# BMS_Carrier_-_Firmware_Contactor_Control.net
KiCad netlist of a schematic drawn in Altium Designer
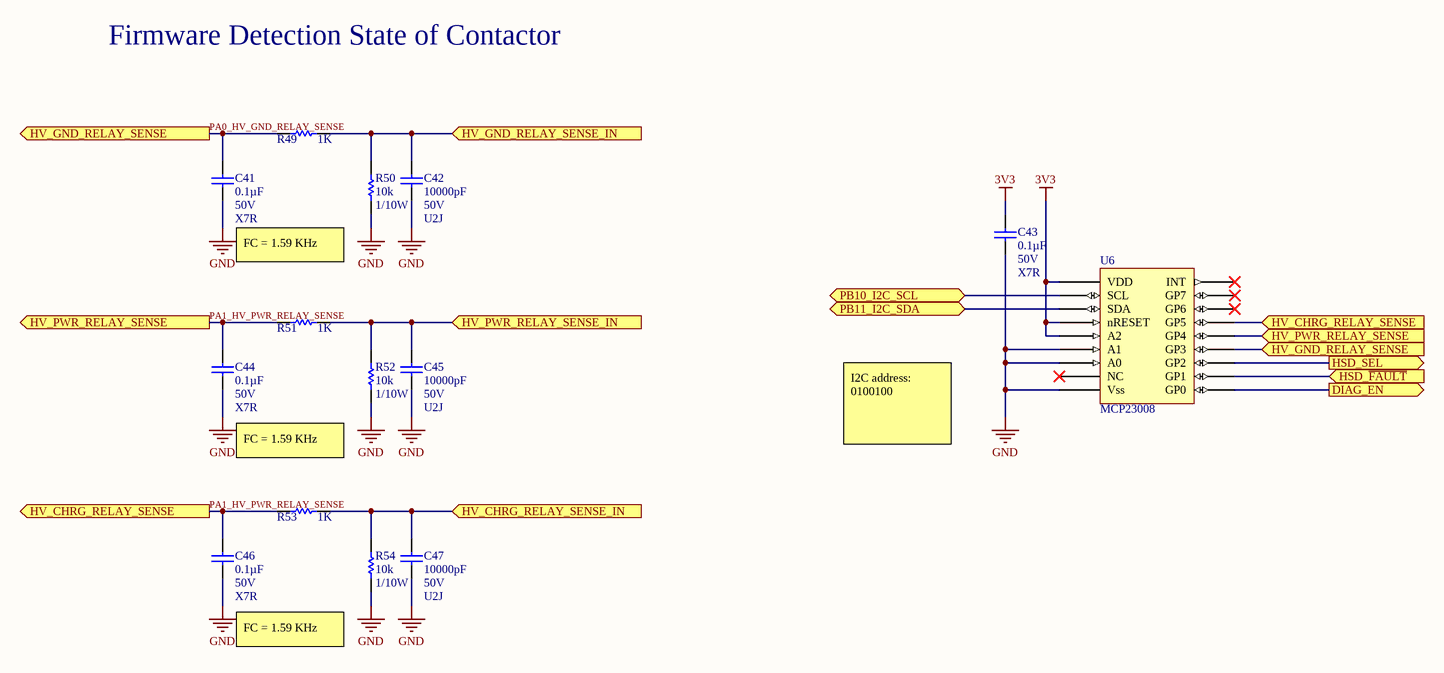
[diagram p0: BMS Carrier - Firmware Contactor Control.SchDoc]

(export (version "E")
  (design (tool "Eeschema 10.0.6"))
  (components
    (comp (ref "C41")
      (value "CAP CER 0.1UF 50V 10% X7R 0603")
      (footprint "CAP, 0603")
      (description "0.10µF ±10% 50V Ceramic Capacitor X7R 0603 (1608 Metric)")
      (fields
        (field (name "TOLERANCE") "±10%")
        (field (name "CAPACITANCE") "0.1µF")
        (field (name "VOLTAGE") "50V")
        (field (name "TEMPERATURE COEFFICIENT") "X7R")
      )
      (libsource (lib "Schematic Diagrams") (part "CAP CER 0.1UF 50V 10% X7R 0603"))
    )
    (comp (ref "C42")
      (value "CAP CER 10nF 50V 5% X7R 0603")
      (footprint "CAP, 0603")
      (description "10000pF ±5% 50V Ceramic Capacitor U2J 0603 (1608 Metric)")
      (fields
        (field (name "TOLERANCE") "±5%")
        (field (name "CAPACITANCE") "10000pF")
        (field (name "VOLTAGE") "50V")
        (field (name "TEMPERATURE COEFFICIENT") "U2J")
      )
      (libsource (lib "Schematic Diagrams") (part "CAP CER 10nF 50V 5% X7R 0603"))
    )
    (comp (ref "C43")
      (value "CAP CER 0.1UF 50V 10% X7R 0603")
      (footprint "CAP, 0603")
      (description "0.10µF ±10% 50V Ceramic Capacitor X7R 0603 (1608 Metric)")
      (fields
        (field (name "TOLERANCE") "±10%")
        (field (name "CAPACITANCE") "0.1µF")
        (field (name "VOLTAGE") "50V")
        (field (name "TEMPERATURE COEFFICIENT") "X7R")
      )
      (libsource (lib "Schematic Diagrams") (part "CAP CER 0.1UF 50V 10% X7R 0603"))
    )
    (comp (ref "C44")
      (value "CAP CER 0.1UF 50V 10% X7R 0603")
      (footprint "CAP, 0603")
      (description "0.10µF ±10% 50V Ceramic Capacitor X7R 0603 (1608 Metric)")
      (fields
        (field (name "TOLERANCE") "±10%")
        (field (name "CAPACITANCE") "0.1µF")
        (field (name "VOLTAGE") "50V")
        (field (name "TEMPERATURE COEFFICIENT") "X7R")
      )
      (libsource (lib "Schematic Diagrams") (part "CAP CER 0.1UF 50V 10% X7R 0603"))
    )
    (comp (ref "C45")
      (value "CAP CER 10nF 50V 5% X7R 0603")
      (footprint "CAP, 0603")
      (description "10000pF ±5% 50V Ceramic Capacitor U2J 0603 (1608 Metric)")
      (fields
        (field (name "TOLERANCE") "±5%")
        (field (name "CAPACITANCE") "10000pF")
        (field (name "VOLTAGE") "50V")
        (field (name "TEMPERATURE COEFFICIENT") "U2J")
      )
      (libsource (lib "Schematic Diagrams") (part "CAP CER 10nF 50V 5% X7R 0603"))
    )
    (comp (ref "C46")
      (value "CAP CER 0.1UF 50V 10% X7R 0603")
      (footprint "CAP, 0603")
      (description "0.10µF ±10% 50V Ceramic Capacitor X7R 0603 (1608 Metric)")
      (fields
        (field (name "TOLERANCE") "±10%")
        (field (name "CAPACITANCE") "0.1µF")
        (field (name "VOLTAGE") "50V")
        (field (name "TEMPERATURE COEFFICIENT") "X7R")
      )
      (libsource (lib "Schematic Diagrams") (part "CAP CER 0.1UF 50V 10% X7R 0603"))
    )
    (comp (ref "C47")
      (value "CAP CER 10nF 50V 5% X7R 0603")
      (footprint "CAP, 0603")
      (description "10000pF ±5% 50V Ceramic Capacitor U2J 0603 (1608 Metric)")
      (fields
        (field (name "TOLERANCE") "±5%")
        (field (name "CAPACITANCE") "10000pF")
        (field (name "VOLTAGE") "50V")
        (field (name "TEMPERATURE COEFFICIENT") "U2J")
      )
      (libsource (lib "Schematic Diagrams") (part "CAP CER 10nF 50V 5% X7R 0603"))
    )
    (comp (ref "R49")
      (value "1K")
      (footprint "RES, 0603")
      (description "1k Ohm ±5% 0.1W, 1/10W Chip Resistor 0603 (1608 Metric)")
      (fields
        (field (name "MANUFACTURER") "Yageo")
        (field (name "MANUFACTURER PART NUMBER") "RC0603JR-071KL")
      )
      (libsource (lib "Schematic Diagrams") (part "RES 1K OHM 5% 1/10W 0603"))
    )
    (comp (ref "R50")
      (value "RES 10K OHM 1% 1/10W 0603")
      (footprint "RES, 0603")
      (description "RES SMD 10K OHM 1% 1/10W 0603")
      (fields
        (field (name "TOLERANCE") "±1%")
        (field (name "RESISTANCE") "10k")
        (field (name "POWER") "1/10W")
      )
      (libsource (lib "Schematic Diagrams") (part "RES 10K OHM 1% 1/10W 0603"))
    )
    (comp (ref "R51")
      (value "1K")
      (footprint "RES, 0603")
      (description "1k Ohm ±5% 0.1W, 1/10W Chip Resistor 0603 (1608 Metric)")
      (fields
        (field (name "MANUFACTURER") "Yageo")
        (field (name "MANUFACTURER PART NUMBER") "RC0603JR-071KL")
      )
      (libsource (lib "Schematic Diagrams") (part "RES 1K OHM 5% 1/10W 0603"))
    )
    (comp (ref "R52")
      (value "RES 10K OHM 1% 1/10W 0603")
      (footprint "RES, 0603")
      (description "RES SMD 10K OHM 1% 1/10W 0603")
      (fields
        (field (name "TOLERANCE") "±1%")
        (field (name "RESISTANCE") "10k")
        (field (name "POWER") "1/10W")
      )
      (libsource (lib "Schematic Diagrams") (part "RES 10K OHM 1% 1/10W 0603"))
    )
    (comp (ref "R53")
      (value "1K")
      (footprint "RES, 0603")
      (description "1k Ohm ±5% 0.1W, 1/10W Chip Resistor 0603 (1608 Metric)")
      (fields
        (field (name "MANUFACTURER") "Yageo")
        (field (name "MANUFACTURER PART NUMBER") "RC0603JR-071KL")
      )
      (libsource (lib "Schematic Diagrams") (part "RES 1K OHM 5% 1/10W 0603"))
    )
    (comp (ref "R54")
      (value "RES 10K OHM 1% 1/10W 0603")
      (footprint "RES, 0603")
      (description "RES SMD 10K OHM 1% 1/10W 0603")
      (fields
        (field (name "TOLERANCE") "±1%")
        (field (name "RESISTANCE") "10k")
        (field (name "POWER") "1/10W")
      )
      (libsource (lib "Schematic Diagrams") (part "RES 10K OHM 1% 1/10W 0603"))
    )
    (comp (ref "U6")
      (value "MCP23008")
      (footprint "IC 18SOIC")
      (description "MCP23008 I/O Expander 8B+1Int 18P SOIC")
      (fields
        (field (name "MANUFACTURER") "Microchip Technology")
        (field (name "MANUFACTURER PART NUMBER") "MCP23008T-E/SO")
      )
      (libsource (lib "Schematic Diagrams") (part "IC I/O EXPANDER I2C 8B 18SOIC"))
    )
  )
  (nets
    (net (code "1") (name "/DIAG_EN") (class "Default")
      (node (ref "U6") (pin "10") (pinfunction "GP0_10") (pintype "bidirectional"))
    )
    (net (code "2") (name "/HSD_SEL") (class "Default")
      (node (ref "U6") (pin "12") (pinfunction "GP2_12") (pintype "bidirectional"))
    )
    (net (code "3") (name "/HSD_~{FAULT}") (class "Default")
      (node (ref "U6") (pin "11") (pinfunction "GP1_11") (pintype "bidirectional"))
    )
    (net (code "4") (name "/HV_CHRG_RELAY_SENSE_IN") (class "Default")
      (node (ref "C47") (pin "1") (pinfunction "1_1") (pintype "passive"))
      (node (ref "R53") (pin "2") (pinfunction "2_2") (pintype "passive"))
      (node (ref "R54") (pin "1") (pinfunction "1_1") (pintype "passive"))
    )
    (net (code "5") (name "/HV_GND_RELAY_SENSE_IN") (class "Default")
      (node (ref "C42") (pin "1") (pinfunction "1_1") (pintype "passive"))
      (node (ref "R49") (pin "2") (pinfunction "2_2") (pintype "passive"))
      (node (ref "R50") (pin "1") (pinfunction "1_1") (pintype "passive"))
    )
    (net (code "6") (name "/HV_PWR_RELAY_SENSE_IN") (class "Default")
      (node (ref "C45") (pin "1") (pinfunction "1_1") (pintype "passive"))
      (node (ref "R51") (pin "2") (pinfunction "2_2") (pintype "passive"))
      (node (ref "R52") (pin "1") (pinfunction "1_1") (pintype "passive"))
    )
    (net (code "7") (name "/PA0_HV_GND_RELAY_SENSE") (class "Default")
      (node (ref "C41") (pin "1") (pinfunction "1_1") (pintype "passive"))
      (node (ref "R49") (pin "1") (pinfunction "1_1") (pintype "passive"))
      (node (ref "U6") (pin "13") (pinfunction "GP3_13") (pintype "bidirectional"))
    )
    (net (code "8") (name "/PA1_HV_PWR_RELAY_SENSE") (class "Default")
      (node (ref "C44") (pin "1") (pinfunction "1_1") (pintype "passive"))
      (node (ref "C46") (pin "1") (pinfunction "1_1") (pintype "passive"))
      (node (ref "R51") (pin "1") (pinfunction "1_1") (pintype "passive"))
      (node (ref "R53") (pin "1") (pinfunction "1_1") (pintype "passive"))
      (node (ref "U6") (pin "14") (pinfunction "GP4_14") (pintype "bidirectional"))
      (node (ref "U6") (pin "15") (pinfunction "GP5_15") (pintype "bidirectional"))
    )
    (net (code "9") (name "/PB10_I2C_SCL") (class "Default")
      (node (ref "U6") (pin "1") (pinfunction "SCL_1") (pintype "bidirectional"))
    )
    (net (code "10") (name "/PB11_I2C_SDA") (class "Default")
      (node (ref "U6") (pin "2") (pinfunction "SDA_2") (pintype "bidirectional"))
    )
    (net (code "11") (name "3V3") (class "Default")
      (node (ref "C43") (pin "1") (pinfunction "1_1") (pintype "passive"))
      (node (ref "U6") (pin "18") (pinfunction "VDD_18") (pintype "power_in"))
      (node (ref "U6") (pin "3") (pinfunction "A2_3") (pintype "input"))
      (node (ref "U6") (pin "6") (pinfunction "nRESET_6") (pintype "input"))
    )
    (net (code "12") (name "GND") (class "Default")
      (node (ref "C41") (pin "2") (pinfunction "2_2") (pintype "passive"))
      (node (ref "C42") (pin "2") (pinfunction "2_2") (pintype "passive"))
      (node (ref "C43") (pin "2") (pinfunction "2_2") (pintype "passive"))
      (node (ref "C44") (pin "2") (pinfunction "2_2") (pintype "passive"))
      (node (ref "C45") (pin "2") (pinfunction "2_2") (pintype "passive"))
      (node (ref "C46") (pin "2") (pinfunction "2_2") (pintype "passive"))
      (node (ref "C47") (pin "2") (pinfunction "2_2") (pintype "passive"))
      (node (ref "R50") (pin "2") (pinfunction "2_2") (pintype "passive"))
      (node (ref "R52") (pin "2") (pinfunction "2_2") (pintype "passive"))
      (node (ref "R54") (pin "2") (pinfunction "2_2") (pintype "passive"))
      (node (ref "U6") (pin "4") (pinfunction "A1_4") (pintype "input"))
      (node (ref "U6") (pin "5") (pinfunction "A0_5") (pintype "input"))
      (node (ref "U6") (pin "9") (pinfunction "Vss_9") (pintype "power_in"))
    )
    (net (code "13") (name "unconnected-(U6-GP6-Pad16)") (class "Default")
      (node (ref "U6") (pin "16") (pinfunction "GP6_16") (pintype "bidirectional+no_connect"))
    )
    (net (code "14") (name "unconnected-(U6-GP7-Pad17)") (class "Default")
      (node (ref "U6") (pin "17") (pinfunction "GP7_17") (pintype "bidirectional+no_connect"))
    )
    (net (code "15") (name "unconnected-(U6-INT-Pad8)") (class "Default")
      (node (ref "U6") (pin "8") (pinfunction "INT_8") (pintype "output+no_connect"))
    )
    (net (code "16") (name "unconnected-(U6-NC-Pad7)") (class "Default")
      (node (ref "U6") (pin "7") (pinfunction "NC_7") (pintype "passive+no_connect"))
    )
  )
)
